# Relay_Module.net
KiCad netlist of a schematic drawn in Altium Designer
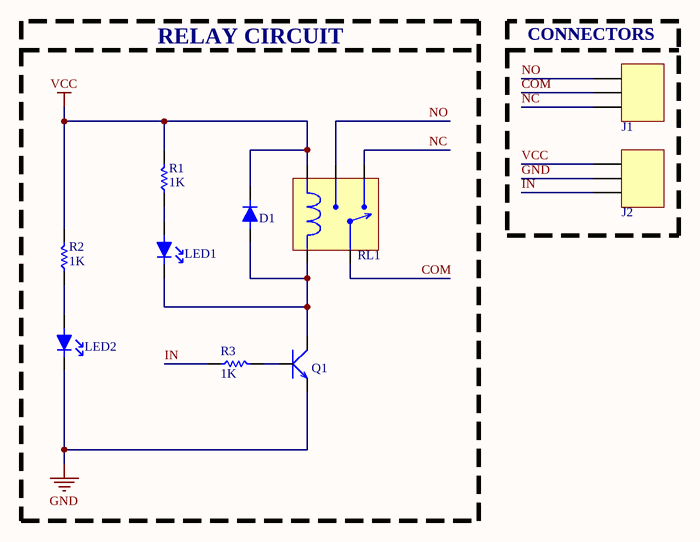
[diagram p0: Relay Module.SchDoc]

(export (version "E")
  (design (tool "Eeschema 10.0.6"))
  (components
    (comp (ref "D1")
      (value "S1A")
      (footprint "DIODE")
      (description "DIODE 50V 1A SMD")
      (libsource (lib "Relay Module") (part "DIODE SMD"))
    )
    (comp (ref "J1")
      (value "OSTTA034163")
      (footprint "connector")
      (description "TERM BLK 3P 5.08MM PCB")
      (libsource (lib "Relay Module") (part "CONNECTOR"))
    )
    (comp (ref "J2")
      (value "61300311121")
      (footprint "HEADER")
      (description "CONN HEADER 3POS 2.54MM")
      (libsource (lib "Relay Module") (part "HEADER"))
    )
    (comp (ref "LED1")
      (value "151031VS06000")
      (footprint "GREEN LED")
      (description "LED GREEN 3MM TH")
      (libsource (lib "Relay Module") (part "GREEN LED TH"))
    )
    (comp (ref "LED2")
      (value "151031SS06000")
      (footprint "RED LED")
      (description "LED RED 3MM TH")
      (libsource (lib "Relay Module") (part "RED LED TH"))
    )
    (comp (ref "Q1")
      (value "PMBT2222A,215")
      (footprint "TRANSISTOR")
      (description "TRANS NPN 30V 0.6A TO236AB")
      (libsource (lib "Relay Module") (part "TRANSISTOR"))
    )
    (comp (ref "R1")
      (value "1K")
      (footprint "RES 0805")
      (description "RES 1K OHM 1% 1/4W 0805")
      (fields (field (name "Comment") "RNCP0805FTD1K00"))
      (libsource (lib "Relay Module") (part "RES 1K OHM 0805 SMD"))
    )
    (comp (ref "R2")
      (value "1K")
      (footprint "RES 0805")
      (description "RES 1K OHM 1% 1/4W 0805")
      (fields (field (name "Comment") "RNCP0805FTD1K00"))
      (libsource (lib "Relay Module") (part "RES 1K OHM 0805 SMD"))
    )
    (comp (ref "R3")
      (value "1K")
      (footprint "RES 0805")
      (description "RES 1K OHM 1% 1/4W 0805")
      (fields (field (name "Comment") "RNCP0805FTD1K00"))
      (libsource (lib "Relay Module") (part "RES 1K OHM 0805 SMD"))
    )
    (comp (ref "RL1")
      (value "G5LE-1 DC5")
      (footprint "RELAY")
      (description "RELAY 5VDC COIL 10A")
      (libsource (lib "Relay Module") (part "RELAY"))
    )
  )
  (nets
    (net (code "1") (name "/COM") (class "Default")
      (node (ref "J1") (pin "2") (pintype "passive"))
      (node (ref "RL1") (pin "1") (pintype "passive"))
    )
    (net (code "2") (name "/IN") (class "Default")
      (node (ref "J2") (pin "3") (pintype "passive"))
      (node (ref "R3") (pin "1") (pintype "passive"))
    )
    (net (code "3") (name "/NC") (class "Default")
      (node (ref "J1") (pin "3") (pintype "passive"))
      (node (ref "RL1") (pin "4") (pintype "passive"))
    )
    (net (code "4") (name "/NO") (class "Default")
      (node (ref "J1") (pin "1") (pintype "passive"))
      (node (ref "RL1") (pin "3") (pintype "passive"))
    )
    (net (code "5") (name "GND") (class "Default")
      (node (ref "J2") (pin "2") (pintype "passive"))
      (node (ref "LED2") (pin "2") (pintype "passive"))
      (node (ref "Q1") (pin "2") (pintype "passive"))
    )
    (net (code "6") (name "Net-(D1-Pad1)") (class "Default")
      (node (ref "D1") (pin "1") (pintype "passive"))
      (node (ref "LED1") (pin "2") (pintype "passive"))
      (node (ref "Q1") (pin "3") (pintype "passive"))
      (node (ref "RL1") (pin "5") (pintype "passive"))
    )
    (net (code "7") (name "Net-(LED1-Pad1)") (class "Default")
      (node (ref "LED1") (pin "1") (pintype "passive"))
      (node (ref "R1") (pin "1") (pintype "passive"))
    )
    (net (code "8") (name "Net-(LED2-Pad1)") (class "Default")
      (node (ref "LED2") (pin "1") (pintype "passive"))
      (node (ref "R2") (pin "1") (pintype "passive"))
    )
    (net (code "9") (name "Net-(Q1-Pad1)") (class "Default")
      (node (ref "Q1") (pin "1") (pintype "passive"))
      (node (ref "R3") (pin "2") (pintype "passive"))
    )
    (net (code "10") (name "VCC") (class "Default")
      (node (ref "D1") (pin "2") (pintype "passive"))
      (node (ref "J2") (pin "1") (pintype "passive"))
      (node (ref "R1") (pin "2") (pintype "passive"))
      (node (ref "R2") (pin "2") (pintype "passive"))
      (node (ref "RL1") (pin "2") (pintype "passive"))
    )
  )
)
